# Mcu.net
KiCad netlist of a schematic drawn in Altium Designer
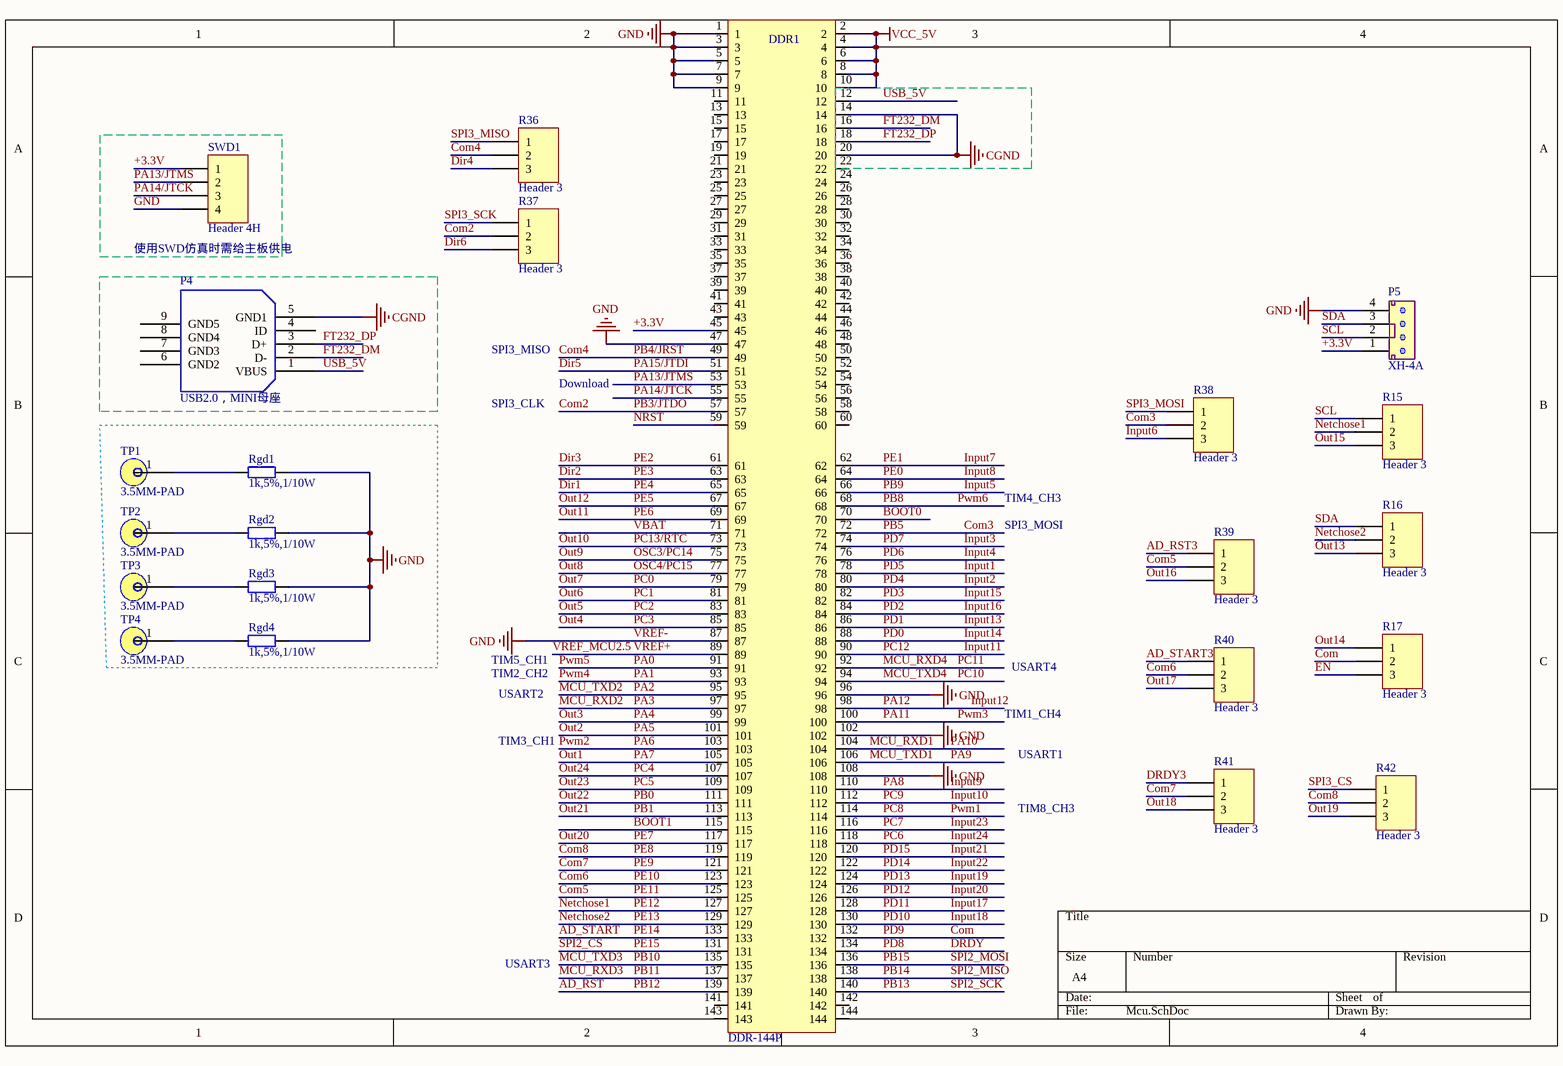
[diagram p0: Mcu.SchDoc]

(export (version "E")
  (design (tool "Eeschema 10.0.6"))
  (components
    (comp (ref "DDR1")
      (value "DDR-144P")
      (footprint "DDRB-144P-0.8MM")
      (libsource (lib "SR SCH Library 141106") (part "DDR-144P"))
    )
    (comp (ref "P4")
      (value "USB2.0，MINI母座")
      (footprint "USB2.0-MINI")
      (description "USB插座,MINI型母座,USB2.0")
      (libsource (lib "SR SCH Library V02") (part "USB2.0-MINI"))
    )
    (comp (ref "P5") (value "XH-4A") (footprint "CN4-3.5") (libsource (lib "元件库-标准") (part "CON4")))
    (comp (ref "R15")
      (value "Header 3")
      (footprint "3P-0603")
      (description "Header, 3-Pin")
      (fields (field (name "PUBLISHER") "Altium Limited"))
      (libsource (lib "Miscellaneous Connectors") (part "Header 3"))
    )
    (comp (ref "R16")
      (value "Header 3")
      (footprint "3P-0603")
      (description "Header, 3-Pin")
      (fields (field (name "PUBLISHER") "Altium Limited"))
      (libsource (lib "Miscellaneous Connectors") (part "Header 3"))
    )
    (comp (ref "R17")
      (value "Header 3")
      (footprint "3P-0603")
      (description "Header, 3-Pin")
      (fields (field (name "PUBLISHER") "Altium Limited"))
      (libsource (lib "Miscellaneous Connectors") (part "Header 3"))
    )
    (comp (ref "R36")
      (value "Header 3")
      (footprint "3P-0603")
      (description "Header, 3-Pin")
      (fields (field (name "PUBLISHER") "Altium Limited"))
      (libsource (lib "Miscellaneous Connectors") (part "Header 3"))
    )
    (comp (ref "R37")
      (value "Header 3")
      (footprint "3P-0603")
      (description "Header, 3-Pin")
      (fields (field (name "PUBLISHER") "Altium Limited"))
      (libsource (lib "Miscellaneous Connectors") (part "Header 3"))
    )
    (comp (ref "R38")
      (value "Header 3")
      (footprint "3P-0603")
      (description "Header, 3-Pin")
      (fields (field (name "PUBLISHER") "Altium Limited"))
      (libsource (lib "Miscellaneous Connectors") (part "Header 3"))
    )
    (comp (ref "R39")
      (value "Header 3")
      (footprint "3P-0603")
      (description "Header, 3-Pin")
      (fields (field (name "PUBLISHER") "Altium Limited"))
      (libsource (lib "Miscellaneous Connectors") (part "Header 3"))
    )
    (comp (ref "R40")
      (value "Header 3")
      (footprint "3P-0603")
      (description "Header, 3-Pin")
      (fields (field (name "PUBLISHER") "Altium Limited"))
      (libsource (lib "Miscellaneous Connectors") (part "Header 3"))
    )
    (comp (ref "R41")
      (value "Header 3")
      (footprint "3P-0603")
      (description "Header, 3-Pin")
      (fields (field (name "PUBLISHER") "Altium Limited"))
      (libsource (lib "Miscellaneous Connectors") (part "Header 3"))
    )
    (comp (ref "R42")
      (value "Header 3")
      (footprint "3P-0603")
      (description "Header, 3-Pin")
      (fields (field (name "PUBLISHER") "Altium Limited"))
      (libsource (lib "Miscellaneous Connectors") (part "Header 3"))
    )
    (comp (ref "Rgd1")
      (value "1k,5%,1/10W")
      (footprint "0603R")
      (description "Metal Film Resistance,金属膜电阻,1K,1%,1/10W,0603")
      (libsource (lib "SR SCH Library V01") (part "R1K-0603"))
    )
    (comp (ref "Rgd2")
      (value "1k,5%,1/10W")
      (footprint "0603R")
      (description "Metal Film Resistance,金属膜电阻,1K,1%,1/10W,0603")
      (libsource (lib "SR SCH Library V01") (part "R1K-0603"))
    )
    (comp (ref "Rgd3")
      (value "1k,5%,1/10W")
      (footprint "0603R")
      (description "Metal Film Resistance,金属膜电阻,1K,1%,1/10W,0603")
      (libsource (lib "SR SCH Library V01") (part "R1K-0603"))
    )
    (comp (ref "Rgd4")
      (value "1k,5%,1/10W")
      (footprint "0603R")
      (description "Metal Film Resistance,金属膜电阻,1K,1%,1/10W,0603")
      (libsource (lib "SR SCH Library V01") (part "R1K-0603"))
    )
    (comp (ref "SWD1")
      (value "Header 4H")
      (footprint "SIP4-2.54mm")
      (description "Header, 4-Pin, Right Angle")
      (fields (field (name "PUBLISHER") "Altium Limited"))
      (libsource (lib "Miscellaneous Connectors") (part "Header 4H"))
    )
    (comp (ref "TP1")
      (value "3.5MM-PAD")
      (footprint "PAD3.5mm")
      (libsource (lib "Next_SCHlib") (part "3.5MM-PAD"))
    )
    (comp (ref "TP2")
      (value "3.5MM-PAD")
      (footprint "PAD3.5mm")
      (libsource (lib "Next_SCHlib") (part "3.5MM-PAD"))
    )
    (comp (ref "TP3")
      (value "3.5MM-PAD")
      (footprint "PAD3.5mm")
      (libsource (lib "Next_SCHlib") (part "3.5MM-PAD"))
    )
    (comp (ref "TP4")
      (value "3.5MM-PAD")
      (footprint "PAD3.5mm")
      (libsource (lib "Next_SCHlib") (part "3.5MM-PAD"))
    )
  )
  (nets
    (net (code "1") (name "/+3.3V") (class "Default")
      (node (ref "DDR1") (pin "45") (pinfunction "45_45") (pintype "passive"))
      (node (ref "P5") (pin "1") (pinfunction "1_1") (pintype "passive"))
      (node (ref "SWD1") (pin "1") (pinfunction "1_1") (pintype "passive"))
    )
    (net (code "2") (name "/AD_RST") (class "Default")
      (node (ref "DDR1") (pin "139") (pinfunction "139_139") (pintype "passive"))
    )
    (net (code "3") (name "/AD_RST3") (class "Default")
      (node (ref "R39") (pin "1") (pinfunction "1_1") (pintype "passive"))
    )
    (net (code "4") (name "/AD_START") (class "Default")
      (node (ref "DDR1") (pin "133") (pinfunction "133_133") (pintype "passive"))
    )
    (net (code "5") (name "/AD_START3") (class "Default")
      (node (ref "R40") (pin "1") (pinfunction "1_1") (pintype "passive"))
    )
    (net (code "6") (name "/BOOT0") (class "Default")
      (node (ref "DDR1") (pin "70") (pinfunction "70_70") (pintype "passive"))
    )
    (net (code "7") (name "/BOOT1") (class "Default")
      (node (ref "DDR1") (pin "115") (pinfunction "115_115") (pintype "passive"))
    )
    (net (code "8") (name "/Com") (class "Default")
      (node (ref "DDR1") (pin "132") (pinfunction "132_132") (pintype "passive"))
      (node (ref "R17") (pin "2") (pinfunction "2_2") (pintype "passive"))
    )
    (net (code "9") (name "/Com2") (class "Default")
      (node (ref "DDR1") (pin "57") (pinfunction "57_57") (pintype "passive"))
      (node (ref "R37") (pin "2") (pinfunction "2_2") (pintype "passive"))
    )
    (net (code "10") (name "/Com3") (class "Default")
      (node (ref "DDR1") (pin "72") (pinfunction "72_72") (pintype "passive"))
      (node (ref "R38") (pin "2") (pinfunction "2_2") (pintype "passive"))
    )
    (net (code "11") (name "/Com4") (class "Default")
      (node (ref "DDR1") (pin "49") (pinfunction "49_49") (pintype "passive"))
      (node (ref "R36") (pin "2") (pinfunction "2_2") (pintype "passive"))
    )
    (net (code "12") (name "/Com5") (class "Default")
      (node (ref "DDR1") (pin "125") (pinfunction "125_125") (pintype "passive"))
      (node (ref "R39") (pin "2") (pinfunction "2_2") (pintype "passive"))
    )
    (net (code "13") (name "/Com6") (class "Default")
      (node (ref "DDR1") (pin "123") (pinfunction "123_123") (pintype "passive"))
      (node (ref "R40") (pin "2") (pinfunction "2_2") (pintype "passive"))
    )
    (net (code "14") (name "/Com7") (class "Default")
      (node (ref "DDR1") (pin "121") (pinfunction "121_121") (pintype "passive"))
      (node (ref "R41") (pin "2") (pinfunction "2_2") (pintype "passive"))
    )
    (net (code "15") (name "/Com8") (class "Default")
      (node (ref "DDR1") (pin "119") (pinfunction "119_119") (pintype "passive"))
      (node (ref "R42") (pin "2") (pinfunction "2_2") (pintype "passive"))
    )
    (net (code "16") (name "/DRDY") (class "Default")
      (node (ref "DDR1") (pin "134") (pinfunction "134_134") (pintype "passive"))
    )
    (net (code "17") (name "/DRDY3") (class "Default")
      (node (ref "R41") (pin "1") (pinfunction "1_1") (pintype "passive"))
    )
    (net (code "18") (name "/Dir1") (class "Default")
      (node (ref "DDR1") (pin "65") (pinfunction "65_65") (pintype "passive"))
    )
    (net (code "19") (name "/Dir2") (class "Default")
      (node (ref "DDR1") (pin "63") (pinfunction "63_63") (pintype "passive"))
    )
    (net (code "20") (name "/Dir3") (class "Default")
      (node (ref "DDR1") (pin "61") (pinfunction "61_61") (pintype "passive"))
    )
    (net (code "21") (name "/Dir4") (class "Default")
      (node (ref "R36") (pin "3") (pinfunction "3_3") (pintype "passive"))
    )
    (net (code "22") (name "/Dir5") (class "Default")
      (node (ref "DDR1") (pin "51") (pinfunction "51_51") (pintype "passive"))
    )
    (net (code "23") (name "/Dir6") (class "Default")
      (node (ref "R37") (pin "3") (pinfunction "3_3") (pintype "passive"))
    )
    (net (code "24") (name "/FT232_DM") (class "Default")
      (node (ref "DDR1") (pin "16") (pinfunction "16_16") (pintype "passive"))
      (node (ref "P4") (pin "2") (pinfunction "D-_2") (pintype "passive"))
    )
    (net (code "25") (name "/FT232_DP") (class "Default")
      (node (ref "DDR1") (pin "18") (pinfunction "18_18") (pintype "passive"))
      (node (ref "P4") (pin "3") (pinfunction "D+_3") (pintype "passive"))
    )
    (net (code "26") (name "/Input1") (class "Default")
      (node (ref "DDR1") (pin "78") (pinfunction "78_78") (pintype "passive"))
    )
    (net (code "27") (name "/Input2") (class "Default")
      (node (ref "DDR1") (pin "80") (pinfunction "80_80") (pintype "passive"))
    )
    (net (code "28") (name "/Input3") (class "Default")
      (node (ref "DDR1") (pin "74") (pinfunction "74_74") (pintype "passive"))
    )
    (net (code "29") (name "/Input4") (class "Default")
      (node (ref "DDR1") (pin "76") (pinfunction "76_76") (pintype "passive"))
    )
    (net (code "30") (name "/Input5") (class "Default")
      (node (ref "DDR1") (pin "66") (pinfunction "66_66") (pintype "passive"))
    )
    (net (code "31") (name "/Input6") (class "Default")
      (node (ref "R38") (pin "3") (pinfunction "3_3") (pintype "passive"))
    )
    (net (code "32") (name "/Input7") (class "Default")
      (node (ref "DDR1") (pin "62") (pinfunction "62_62") (pintype "passive"))
    )
    (net (code "33") (name "/Input8") (class "Default")
      (node (ref "DDR1") (pin "64") (pinfunction "64_64") (pintype "passive"))
    )
    (net (code "34") (name "/Input9") (class "Default")
      (node (ref "DDR1") (pin "110") (pinfunction "110_110") (pintype "passive"))
    )
    (net (code "35") (name "/Input10") (class "Default")
      (node (ref "DDR1") (pin "112") (pinfunction "112_112") (pintype "passive"))
    )
    (net (code "36") (name "/Input11") (class "Default")
      (node (ref "DDR1") (pin "90") (pinfunction "90_90") (pintype "passive"))
    )
    (net (code "37") (name "/Input12") (class "Default")
      (node (ref "DDR1") (pin "98") (pinfunction "98_98") (pintype "passive"))
    )
    (net (code "38") (name "/Input13") (class "Default")
      (node (ref "DDR1") (pin "86") (pinfunction "86_86") (pintype "passive"))
    )
    (net (code "39") (name "/Input14") (class "Default")
      (node (ref "DDR1") (pin "88") (pinfunction "88_88") (pintype "passive"))
    )
    (net (code "40") (name "/Input15") (class "Default")
      (node (ref "DDR1") (pin "82") (pinfunction "82_82") (pintype "passive"))
    )
    (net (code "41") (name "/Input16") (class "Default")
      (node (ref "DDR1") (pin "84") (pinfunction "84_84") (pintype "passive"))
    )
    (net (code "42") (name "/Input17") (class "Default")
      (node (ref "DDR1") (pin "128") (pinfunction "128_128") (pintype "passive"))
    )
    (net (code "43") (name "/Input18") (class "Default")
      (node (ref "DDR1") (pin "130") (pinfunction "130_130") (pintype "passive"))
    )
    (net (code "44") (name "/Input19") (class "Default")
      (node (ref "DDR1") (pin "124") (pinfunction "124_124") (pintype "passive"))
    )
    (net (code "45") (name "/Input20") (class "Default")
      (node (ref "DDR1") (pin "126") (pinfunction "126_126") (pintype "passive"))
    )
    (net (code "46") (name "/Input21") (class "Default")
      (node (ref "DDR1") (pin "120") (pinfunction "120_120") (pintype "passive"))
    )
    (net (code "47") (name "/Input22") (class "Default")
      (node (ref "DDR1") (pin "122") (pinfunction "122_122") (pintype "passive"))
    )
    (net (code "48") (name "/Input23") (class "Default")
      (node (ref "DDR1") (pin "116") (pinfunction "116_116") (pintype "passive"))
    )
    (net (code "49") (name "/Input24") (class "Default")
      (node (ref "DDR1") (pin "118") (pinfunction "118_118") (pintype "passive"))
    )
    (net (code "50") (name "/MCU_RXD1") (class "Default")
      (node (ref "DDR1") (pin "104") (pinfunction "104_104") (pintype "passive"))
    )
    (net (code "51") (name "/MCU_RXD2") (class "Default")
      (node (ref "DDR1") (pin "97") (pinfunction "97_97") (pintype "passive"))
    )
    (net (code "52") (name "/MCU_RXD3") (class "Default")
      (node (ref "DDR1") (pin "137") (pinfunction "137_137") (pintype "passive"))
    )
    (net (code "53") (name "/MCU_RXD4") (class "Default")
      (node (ref "DDR1") (pin "92") (pinfunction "92_92") (pintype "passive"))
    )
    (net (code "54") (name "/MCU_TXD1") (class "Default")
      (node (ref "DDR1") (pin "106") (pinfunction "106_106") (pintype "passive"))
    )
    (net (code "55") (name "/MCU_TXD2") (class "Default")
      (node (ref "DDR1") (pin "95") (pinfunction "95_95") (pintype "passive"))
    )
    (net (code "56") (name "/MCU_TXD3") (class "Default")
      (node (ref "DDR1") (pin "135") (pinfunction "135_135") (pintype "passive"))
    )
    (net (code "57") (name "/MCU_TXD4") (class "Default")
      (node (ref "DDR1") (pin "94") (pinfunction "94_94") (pintype "passive"))
    )
    (net (code "58") (name "/NRST") (class "Default")
      (node (ref "DDR1") (pin "59") (pinfunction "59_59") (pintype "passive"))
    )
    (net (code "59") (name "/Netchose1") (class "Default")
      (node (ref "DDR1") (pin "127") (pinfunction "127_127") (pintype "passive"))
      (node (ref "R15") (pin "2") (pinfunction "2_2") (pintype "passive"))
    )
    (net (code "60") (name "/Netchose2") (class "Default")
      (node (ref "DDR1") (pin "129") (pinfunction "129_129") (pintype "passive"))
      (node (ref "R16") (pin "2") (pinfunction "2_2") (pintype "passive"))
    )
    (net (code "61") (name "/OSC3{slash}PC14") (class "Default")
      (node (ref "DDR1") (pin "75") (pinfunction "75_75") (pintype "passive"))
    )
    (net (code "62") (name "/OSC4{slash}PC15") (class "Default")
      (node (ref "DDR1") (pin "77") (pinfunction "77_77") (pintype "passive"))
    )
    (net (code "63") (name "/Out1") (class "Default")
      (node (ref "DDR1") (pin "105") (pinfunction "105_105") (pintype "passive"))
    )
    (net (code "64") (name "/Out2") (class "Default")
      (node (ref "DDR1") (pin "101") (pinfunction "101_101") (pintype "passive"))
    )
    (net (code "65") (name "/Out3") (class "Default")
      (node (ref "DDR1") (pin "99") (pinfunction "99_99") (pintype "passive"))
    )
    (net (code "66") (name "/Out4") (class "Default")
      (node (ref "DDR1") (pin "85") (pinfunction "85_85") (pintype "passive"))
    )
    (net (code "67") (name "/Out5") (class "Default")
      (node (ref "DDR1") (pin "83") (pinfunction "83_83") (pintype "passive"))
    )
    (net (code "68") (name "/Out6") (class "Default")
      (node (ref "DDR1") (pin "81") (pinfunction "81_81") (pintype "passive"))
    )
    (net (code "69") (name "/Out7") (class "Default")
      (node (ref "DDR1") (pin "79") (pinfunction "79_79") (pintype "passive"))
    )
    (net (code "70") (name "/Out10") (class "Default")
      (node (ref "DDR1") (pin "73") (pinfunction "73_73") (pintype "passive"))
    )
    (net (code "71") (name "/Out11") (class "Default")
      (node (ref "DDR1") (pin "69") (pinfunction "69_69") (pintype "passive"))
    )
    (net (code "72") (name "/Out12") (class "Default")
      (node (ref "DDR1") (pin "67") (pinfunction "67_67") (pintype "passive"))
    )
    (net (code "73") (name "/Out13") (class "Default")
      (node (ref "R16") (pin "3") (pinfunction "3_3") (pintype "passive"))
    )
    (net (code "74") (name "/Out14") (class "Default")
      (node (ref "R17") (pin "1") (pinfunction "1_1") (pintype "passive"))
    )
    (net (code "75") (name "/Out15") (class "Default")
      (node (ref "R15") (pin "3") (pinfunction "3_3") (pintype "passive"))
    )
    (net (code "76") (name "/Out16") (class "Default")
      (node (ref "R39") (pin "3") (pinfunction "3_3") (pintype "passive"))
    )
    (net (code "77") (name "/Out17") (class "Default")
      (node (ref "R40") (pin "3") (pinfunction "3_3") (pintype "passive"))
    )
    (net (code "78") (name "/Out18") (class "Default")
      (node (ref "R41") (pin "3") (pinfunction "3_3") (pintype "passive"))
    )
    (net (code "79") (name "/Out19") (class "Default")
      (node (ref "R42") (pin "3") (pinfunction "3_3") (pintype "passive"))
    )
    (net (code "80") (name "/Out20") (class "Default")
      (node (ref "DDR1") (pin "117") (pinfunction "117_117") (pintype "passive"))
    )
    (net (code "81") (name "/Out21") (class "Default")
      (node (ref "DDR1") (pin "113") (pinfunction "113_113") (pintype "passive"))
    )
    (net (code "82") (name "/Out22") (class "Default")
      (node (ref "DDR1") (pin "111") (pinfunction "111_111") (pintype "passive"))
    )
    (net (code "83") (name "/Out23") (class "Default")
      (node (ref "DDR1") (pin "109") (pinfunction "109_109") (pintype "passive"))
    )
    (net (code "84") (name "/Out24") (class "Default")
      (node (ref "DDR1") (pin "107") (pinfunction "107_107") (pintype "passive"))
    )
    (net (code "85") (name "/PA0") (class "Default")
      (node (ref "DDR1") (pin "91") (pinfunction "91_91") (pintype "passive"))
    )
    (net (code "86") (name "/PA1") (class "Default")
      (node (ref "DDR1") (pin "93") (pinfunction "93_93") (pintype "passive"))
    )
    (net (code "87") (name "/PA6") (class "Default")
      (node (ref "DDR1") (pin "103") (pinfunction "103_103") (pintype "passive"))
    )
    (net (code "88") (name "/PA11") (class "Default")
      (node (ref "DDR1") (pin "100") (pinfunction "100_100") (pintype "passive"))
    )
    (net (code "89") (name "/PA13{slash}JTMS") (class "Default")
      (node (ref "DDR1") (pin "53") (pinfunction "53_53") (pintype "passive"))
      (node (ref "SWD1") (pin "2") (pinfunction "2_2") (pintype "passive"))
    )
    (net (code "90") (name "/PA14{slash}JTCK") (class "Default")
      (node (ref "DDR1") (pin "55") (pinfunction "55_55") (pintype "passive"))
      (node (ref "SWD1") (pin "3") (pinfunction "3_3") (pintype "passive"))
    )
    (net (code "91") (name "/PB8") (class "Default")
      (node (ref "DDR1") (pin "68") (pinfunction "68_68") (pintype "passive"))
    )
    (net (code "92") (name "/PB13") (class "Default")
      (node (ref "DDR1") (pin "140") (pinfunction "140_140") (pintype "passive"))
    )
    (net (code "93") (name "/PB14") (class "Default")
      (node (ref "DDR1") (pin "138") (pinfunction "138_138") (pintype "passive"))
    )
    (net (code "94") (name "/PB15") (class "Default")
      (node (ref "DDR1") (pin "136") (pinfunction "136_136") (pintype "passive"))
    )
    (net (code "95") (name "/PC8") (class "Default")
      (node (ref "DDR1") (pin "114") (pinfunction "114_114") (pintype "passive"))
    )
    (net (code "96") (name "/PE15") (class "Default")
      (node (ref "DDR1") (pin "131") (pinfunction "131_131") (pintype "passive"))
    )
    (net (code "97") (name "/SCL") (class "Default")
      (node (ref "P5") (pin "2") (pinfunction "2_2") (pintype "passive"))
      (node (ref "R15") (pin "1") (pinfunction "1_1") (pintype "passive"))
    )
    (net (code "98") (name "/SDA") (class "Default")
      (node (ref "P5") (pin "3") (pinfunction "3_3") (pintype "passive"))
      (node (ref "R16") (pin "1") (pinfunction "1_1") (pintype "passive"))
    )
    (net (code "99") (name "/SPI3_CS") (class "Default")
      (node (ref "R42") (pin "1") (pinfunction "1_1") (pintype "passive"))
    )
    (net (code "100") (name "/SPI3_MISO") (class "Default")
      (node (ref "R36") (pin "1") (pinfunction "1_1") (pintype "passive"))
    )
    (net (code "101") (name "/SPI3_MOSI") (class "Default")
      (node (ref "R38") (pin "1") (pinfunction "1_1") (pintype "passive"))
    )
    (net (code "102") (name "/SPI3_SCK") (class "Default")
      (node (ref "R37") (pin "1") (pinfunction "1_1") (pintype "passive"))
    )
    (net (code "103") (name "/USB_5V") (class "Default")
      (node (ref "DDR1") (pin "12") (pinfunction "12_12") (pintype "passive"))
      (node (ref "P4") (pin "1") (pinfunction "VBUS_1") (pintype "passive"))
    )
    (net (code "104") (name "/VBAT") (class "Default")
      (node (ref "DDR1") (pin "71") (pinfunction "71_71") (pintype "passive"))
    )
    (net (code "105") (name "/VREF+") (class "Default")
      (node (ref "DDR1") (pin "89") (pinfunction "89_89") (pintype "passive"))
    )
    (net (code "106") (name "/~{EN}") (class "Default")
      (node (ref "R17") (pin "3") (pinfunction "3_3") (pintype "passive"))
    )
    (net (code "107") (name "CGND") (class "Default")
      (node (ref "DDR1") (pin "14") (pinfunction "14_14") (pintype "passive"))
      (node (ref "DDR1") (pin "20") (pinfunction "20_20") (pintype "passive"))
      (node (ref "P4") (pin "5") (pinfunction "GND1_5") (pintype "passive"))
    )
    (net (code "108") (name "GND") (class "Default")
      (node (ref "DDR1") (pin "1") (pinfunction "1_1") (pintype "passive"))
      (node (ref "DDR1") (pin "102") (pinfunction "102_102") (pintype "passive"))
      (node (ref "DDR1") (pin "108") (pinfunction "108_108") (pintype "passive"))
      (node (ref "DDR1") (pin "3") (pinfunction "3_3") (pintype "passive"))
      (node (ref "DDR1") (pin "47") (pinfunction "47_47") (pintype "passive"))
      (node (ref "DDR1") (pin "5") (pinfunction "5_5") (pintype "passive"))
      (node (ref "DDR1") (pin "7") (pinfunction "7_7") (pintype "passive"))
      (node (ref "DDR1") (pin "87") (pinfunction "87_87") (pintype "passive"))
      (node (ref "DDR1") (pin "9") (pinfunction "9_9") (pintype "passive"))
      (node (ref "DDR1") (pin "96") (pinfunction "96_96") (pintype "passive"))
      (node (ref "P5") (pin "4") (pinfunction "4_4") (pintype "passive"))
      (node (ref "Rgd1") (pin "2") (pinfunction "2_2") (pintype "passive"))
      (node (ref "Rgd2") (pin "2") (pinfunction "2_2") (pintype "passive"))
      (node (ref "Rgd3") (pin "2") (pinfunction "2_2") (pintype "passive"))
      (node (ref "Rgd4") (pin "2") (pinfunction "2_2") (pintype "passive"))
      (node (ref "SWD1") (pin "4") (pinfunction "4_4") (pintype "passive"))
    )
    (net (code "109") (name "Net-(Rgd1-Pad1)") (class "Default")
      (node (ref "Rgd1") (pin "1") (pinfunction "1_1") (pintype "passive"))
      (node (ref "TP1") (pin "1") (pinfunction "1_1") (pintype "passive"))
    )
    (net (code "110") (name "Net-(Rgd2-Pad1)") (class "Default")
      (node (ref "Rgd2") (pin "1") (pinfunction "1_1") (pintype "passive"))
      (node (ref "TP2") (pin "1") (pinfunction "1_1") (pintype "passive"))
    )
    (net (code "111") (name "Net-(Rgd3-Pad1)") (class "Default")
      (node (ref "Rgd3") (pin "1") (pinfunction "1_1") (pintype "passive"))
      (node (ref "TP3") (pin "1") (pinfunction "1_1") (pintype "passive"))
    )
    (net (code "112") (name "Net-(Rgd4-Pad1)") (class "Default")
      (node (ref "Rgd4") (pin "1") (pinfunction "1_1") (pintype "passive"))
      (node (ref "TP4") (pin "1") (pinfunction "1_1") (pintype "passive"))
    )
    (net (code "113") (name "VCC_5V") (class "Default")
      (node (ref "DDR1") (pin "10") (pinfunction "10_10") (pintype "passive"))
      (node (ref "DDR1") (pin "2") (pinfunction "2_2") (pintype "passive"))
      (node (ref "DDR1") (pin "4") (pinfunction "4_4") (pintype "passive"))
      (node (ref "DDR1") (pin "6") (pinfunction "6_6") (pintype "passive"))
      (node (ref "DDR1") (pin "8") (pinfunction "8_8") (pintype "passive"))
    )
    (net (code "114") (name "unconnected-(DDR1-Pad11)") (class "Default")
      (node (ref "DDR1") (pin "11") (pinfunction "11_11") (pintype "passive"))
    )
    (net (code "115") (name "unconnected-(DDR1-Pad13)") (class "Default")
      (node (ref "DDR1") (pin "13") (pinfunction "13_13") (pintype "passive"))
    )
    (net (code "116") (name "unconnected-(DDR1-Pad15)") (class "Default")
      (node (ref "DDR1") (pin "15") (pinfunction "15_15") (pintype "passive"))
    )
    (net (code "117") (name "unconnected-(DDR1-Pad17)") (class "Default")
      (node (ref "DDR1") (pin "17") (pinfunction "17_17") (pintype "passive"))
    )
    (net (code "118") (name "unconnected-(DDR1-Pad19)") (class "Default")
      (node (ref "DDR1") (pin "19") (pinfunction "19_19") (pintype "passive"))
    )
    (net (code "119") (name "unconnected-(DDR1-Pad21)") (class "Default")
      (node (ref "DDR1") (pin "21") (pinfunction "21_21") (pintype "passive"))
    )
    (net (code "120") (name "unconnected-(DDR1-Pad22)") (class "Default")
      (node (ref "DDR1") (pin "22") (pinfunction "22_22") (pintype "passive"))
    )
    (net (code "121") (name "unconnected-(DDR1-Pad23)") (class "Default")
      (node (ref "DDR1") (pin "23") (pinfunction "23_23") (pintype "passive"))
    )
    (net (code "122") (name "unconnected-(DDR1-Pad24)") (class "Default")
      (node (ref "DDR1") (pin "24") (pinfunction "24_24") (pintype "passive"))
    )
    (net (code "123") (name "unconnected-(DDR1-Pad25)") (class "Default")
      (node (ref "DDR1") (pin "25") (pinfunction "25_25") (pintype "passive"))
    )
    (net (code "124") (name "unconnected-(DDR1-Pad26)") (class "Default")
      (node (ref "DDR1") (pin "26") (pinfunction "26_26") (pintype "passive"))
    )
    (net (code "125") (name "unconnected-(DDR1-Pad27)") (class "Default")
      (node (ref "DDR1") (pin "27") (pinfunction "27_27") (pintype "passive"))
    )
    (net (code "126") (name "unconnected-(DDR1-Pad28)") (class "Default")
      (node (ref "DDR1") (pin "28") (pinfunction "28_28") (pintype "passive"))
    )
    (net (code "127") (name "unconnected-(DDR1-Pad29)") (class "Default")
      (node (ref "DDR1") (pin "29") (pinfunction "29_29") (pintype "passive"))
    )
    (net (code "128") (name "unconnected-(DDR1-Pad30)") (class "Default")
      (node (ref "DDR1") (pin "30") (pinfunction "30_30") (pintype "passive"))
    )
    (net (code "129") (name "unconnected-(DDR1-Pad31)") (class "Default")
      (node (ref "DDR1") (pin "31") (pinfunction "31_31") (pintype "passive"))
    )
    (net (code "130") (name "unconnected-(DDR1-Pad32)") (class "Default")
      (node (ref "DDR1") (pin "32") (pinfunction "32_32") (pintype "passive"))
    )
    (net (code "131") (name "unconnected-(DDR1-Pad33)") (class "Default")
      (node (ref "DDR1") (pin "33") (pinfunction "33_33") (pintype "passive"))
    )
    (net (code "132") (name "unconnected-(DDR1-Pad34)") (class "Default")
      (node (ref "DDR1") (pin "34") (pinfunction "34_34") (pintype "passive"))
    )
    (net (code "133") (name "unconnected-(DDR1-Pad35)") (class "Default")
      (node (ref "DDR1") (pin "35") (pinfunction "35_35") (pintype "passive"))
    )
    (net (code "134") (name "unconnected-(DDR1-Pad36)") (class "Default")
      (node (ref "DDR1") (pin "36") (pinfunction "36_36") (pintype "passive"))
    )
    (net (code "135") (name "unconnected-(DDR1-Pad37)") (class "Default")
      (node (ref "DDR1") (pin "37") (pinfunction "37_37") (pintype "passive"))
    )
    (net (code "136") (name "unconnected-(DDR1-Pad38)") (class "Default")
      (node (ref "DDR1") (pin "38") (pinfunction "38_38") (pintype "passive"))
    )
    (net (code "137") (name "unconnected-(DDR1-Pad39)") (class "Default")
      (node (ref "DDR1") (pin "39") (pinfunction "39_39") (pintype "passive"))
    )
    (net (code "138") (name "unconnected-(DDR1-Pad40)") (class "Default")
      (node (ref "DDR1") (pin "40") (pinfunction "40_40") (pintype "passive"))
    )
    (net (code "139") (name "unconnected-(DDR1-Pad41)") (class "Default")
      (node (ref "DDR1") (pin "41") (pinfunction "41_41") (pintype "passive"))
    )
    (net (code "140") (name "unconnected-(DDR1-Pad42)") (class "Default")
      (node (ref "DDR1") (pin "42") (pinfunction "42_42") (pintype "passive"))
    )
    (net (code "141") (name "unconnected-(DDR1-Pad43)") (class "Default")
      (node (ref "DDR1") (pin "43") (pinfunction "43_43") (pintype "passive"))
    )
    (net (code "142") (name "unconnected-(DDR1-Pad44)") (class "Default")
      (node (ref "DDR1") (pin "44") (pinfunction "44_44") (pintype "passive"))
    )
    (net (code "143") (name "unconnected-(DDR1-Pad46)") (class "Default")
      (node (ref "DDR1") (pin "46") (pinfunction "46_46") (pintype "passive"))
    )
    (net (code "144") (name "unconnected-(DDR1-Pad48)") (class "Default")
      (node (ref "DDR1") (pin "48") (pinfunction "48_48") (pintype "passive"))
    )
    (net (code "145") (name "unconnected-(DDR1-Pad50)") (class "Default")
      (node (ref "DDR1") (pin "50") (pinfunction "50_50") (pintype "passive"))
    )
    (net (code "146") (name "unconnected-(DDR1-Pad52)") (class "Default")
      (node (ref "DDR1") (pin "52") (pinfunction "52_52") (pintype "passive"))
    )
    (net (code "147") (name "unconnected-(DDR1-Pad54)") (class "Default")
      (node (ref "DDR1") (pin "54") (pinfunction "54_54") (pintype "passive"))
    )
    (net (code "148") (name "unconnected-(DDR1-Pad56)") (class "Default")
      (node (ref "DDR1") (pin "56") (pinfunction "56_56") (pintype "passive"))
    )
    (net (code "149") (name "unconnected-(DDR1-Pad58)") (class "Default")
      (node (ref "DDR1") (pin "58") (pinfunction "58_58") (pintype "passive"))
    )
    (net (code "150") (name "unconnected-(DDR1-Pad60)") (class "Default")
      (node (ref "DDR1") (pin "60") (pinfunction "60_60") (pintype "passive"))
    )
    (net (code "151") (name "unconnected-(DDR1-Pad141)") (class "Default")
      (node (ref "DDR1") (pin "141") (pinfunction "141_141") (pintype "passive"))
    )
    (net (code "152") (name "unconnected-(DDR1-Pad142)") (class "Default")
      (node (ref "DDR1") (pin "142") (pinfunction "142_142") (pintype "passive"))
    )
    (net (code "153") (name "unconnected-(DDR1-Pad143)") (class "Default")
      (node (ref "DDR1") (pin "143") (pinfunction "143_143") (pintype "passive"))
    )
    (net (code "154") (name "unconnected-(DDR1-Pad144)") (class "Default")
      (node (ref "DDR1") (pin "144") (pinfunction "144_144") (pintype "passive"))
    )
    (net (code "155") (name "unconnected-(P4-GND2-Pad6)") (class "Default")
      (node (ref "P4") (pin "6") (pinfunction "GND2_6") (pintype "passive"))
    )
    (net (code "156") (name "unconnected-(P4-GND3-Pad7)") (class "Default")
      (node (ref "P4") (pin "7") (pinfunction "GND3_7") (pintype "passive"))
    )
    (net (code "157") (name "unconnected-(P4-GND4-Pad8)") (class "Default")
      (node (ref "P4") (pin "8") (pinfunction "GND4_8") (pintype "passive"))
    )
    (net (code "158") (name "unconnected-(P4-GND5-Pad9)") (class "Default")
      (node (ref "P4") (pin "9") (pinfunction "GND5_9") (pintype "passive"))
    )
    (net (code "159") (name "unconnected-(P4-ID-Pad4)") (class "Default")
      (node (ref "P4") (pin "4") (pinfunction "ID_4") (pintype "passive"))
    )
  )
)
